# SCH.net
KiCad netlist of a schematic drawn in EasyEDA
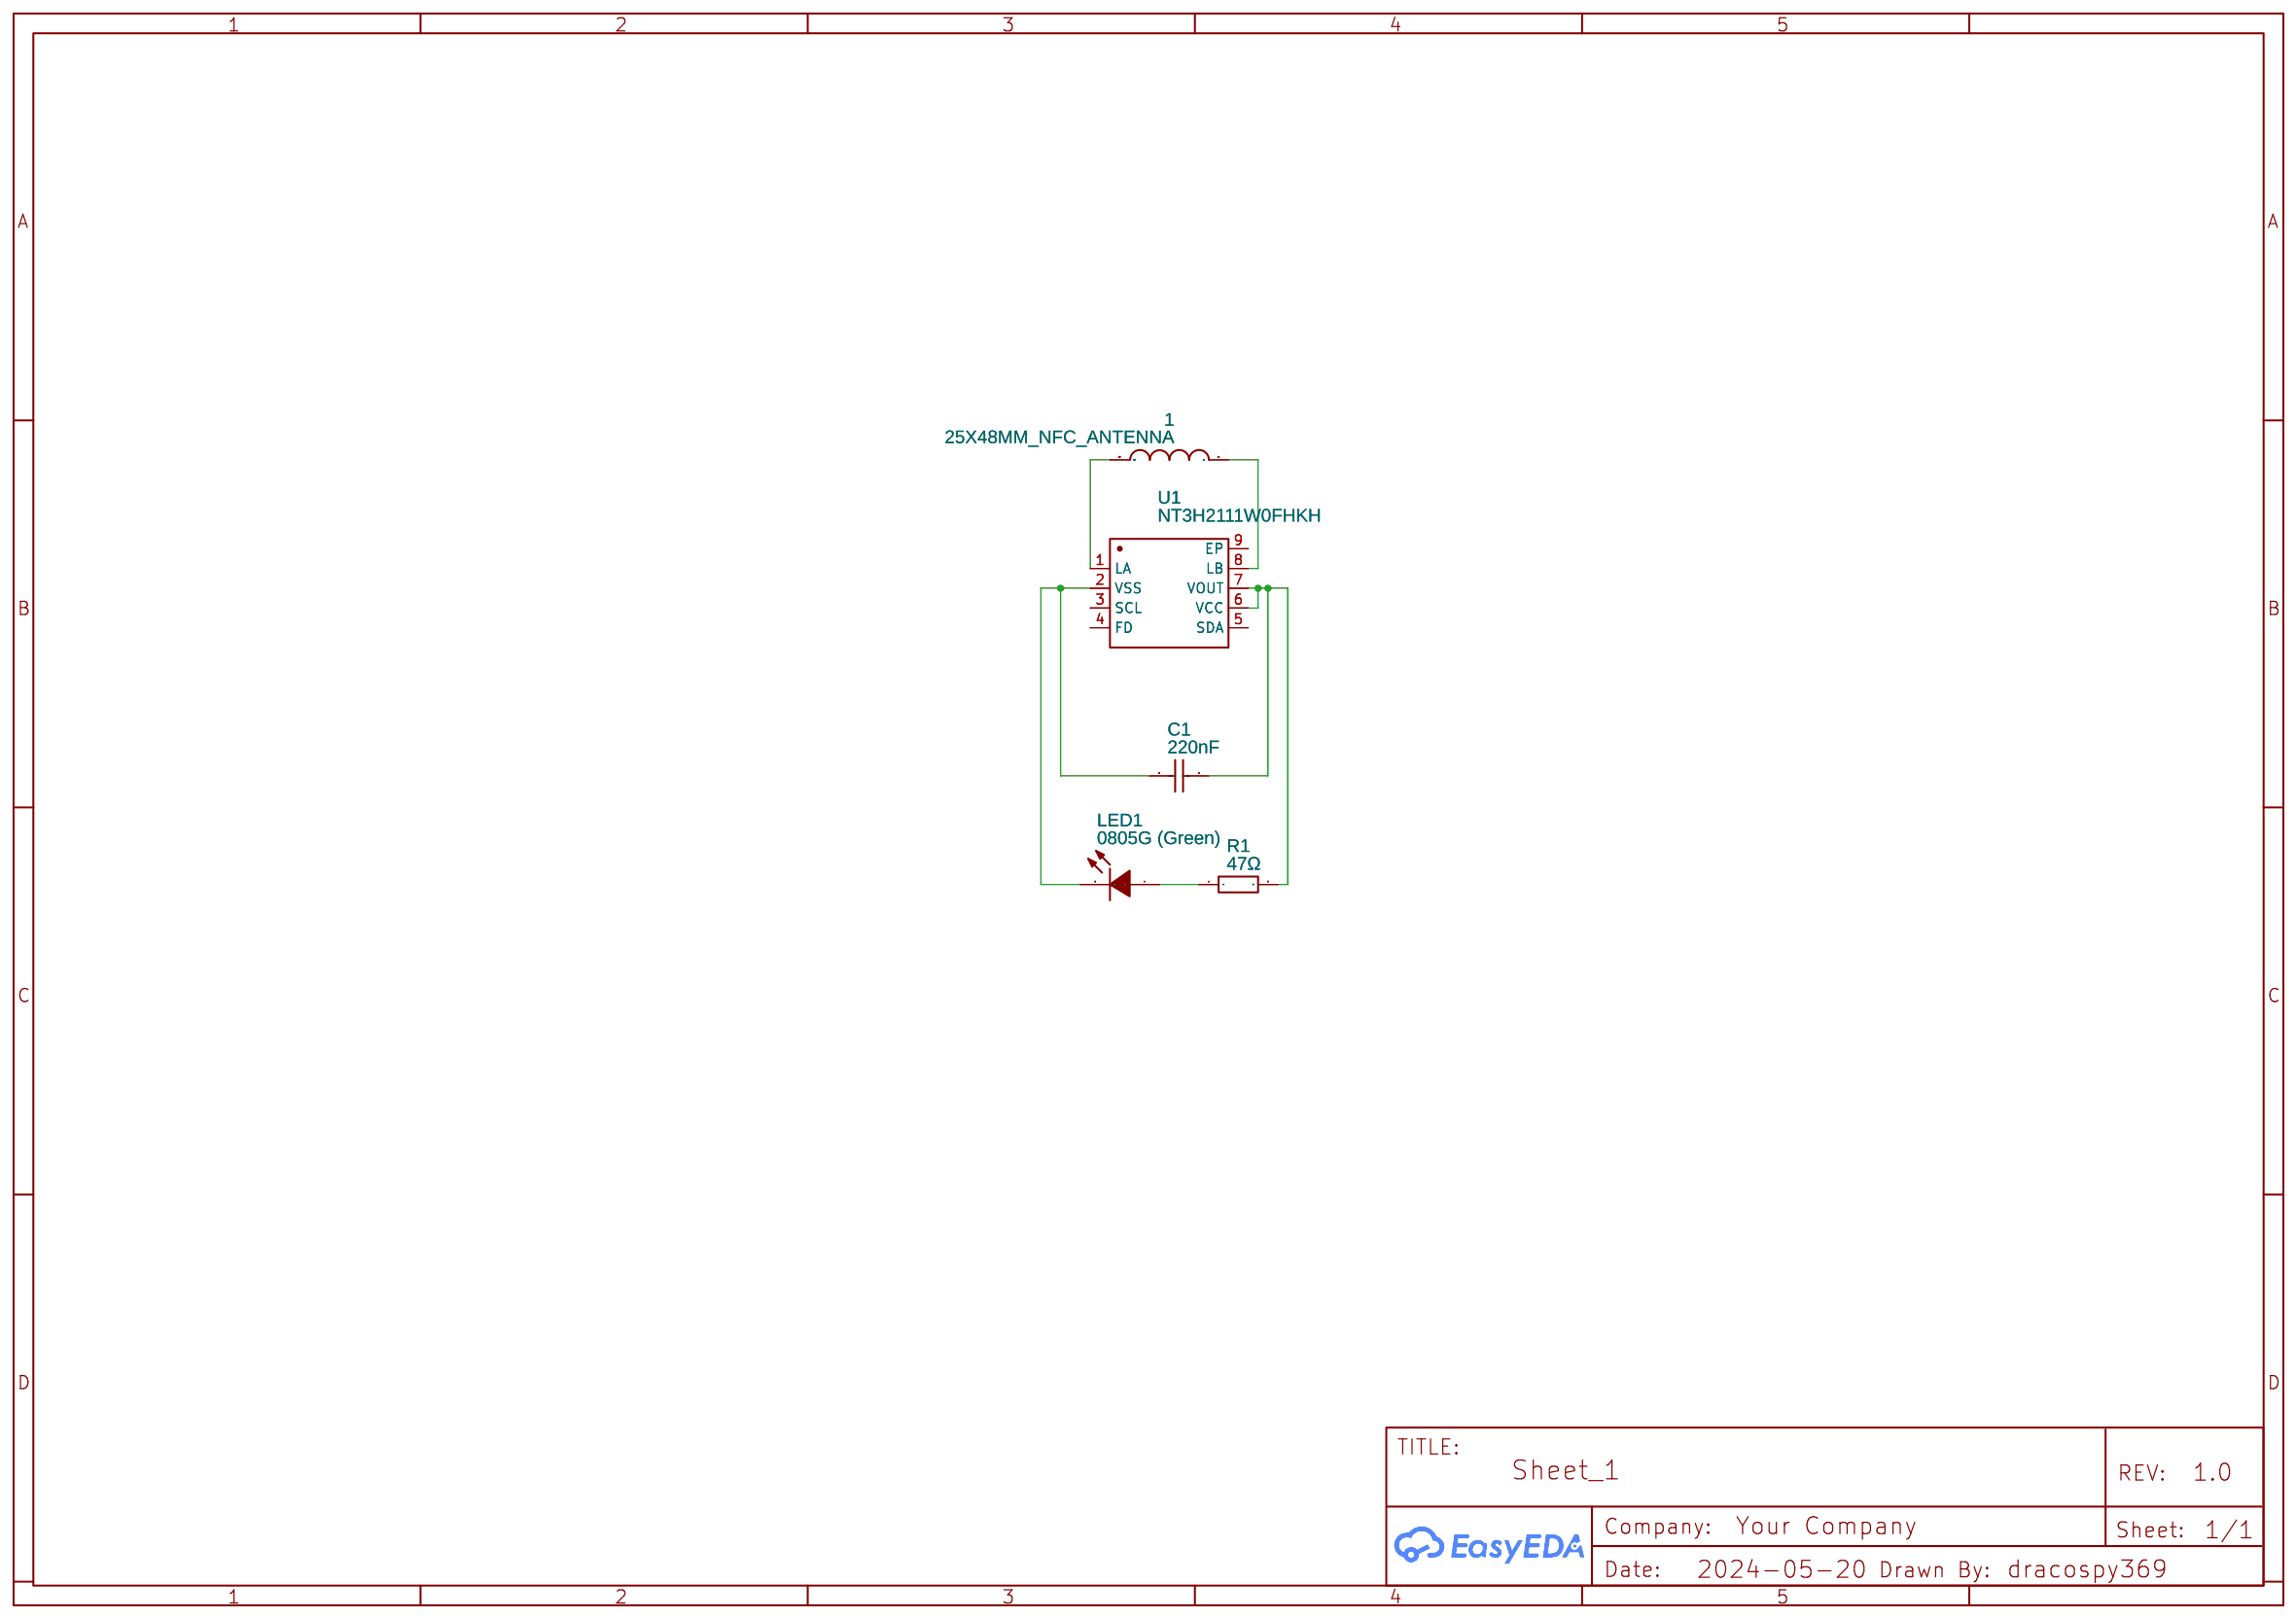
[diagram p0: schematic sheet]

(export (version "E")
  (design (tool "Eeschema 10.0.6"))
  (components
    (comp (ref "1") (value "25X48MM_NFC_ANTENNA") (libsource (lib "") (part "25X48MM_NFC_ANTENNA")))
    (comp (ref "C1")
      (value "220nF")
      (fields
        (field (name "Manufacturer Part") "CL10B224KA8NNNC")
        (field (name "Manufacturer") "SAMSUNG(三星)")
      )
      (libsource (lib "") (part "CL10B224KA8NNNC"))
    )
    (comp (ref "LED1")
      (value "0805G (Green)")
      (fields (field (name "Manufacturer Part") "KT-0805G") (field (name "Manufacturer") "KENTO"))
      (libsource (lib "") (part "0805G (Green)"))
    )
    (comp (ref "R1")
      (value "47Ω")
      (fields
        (field (name "Manufacturer Part") "0603WAF470JT5E")
        (field (name "Manufacturer") "UNI-ROYAL(厚声)")
      )
      (libsource (lib "") (part "0603WAF470JT5E"))
    )
    (comp (ref "U1")
      (value "NT3H2111W0FHKH")
      (fields (field (name "Manufacturer") "NXP(恩智浦)"))
      (libsource (lib "") (part "NT3H2111W0FHKH"))
    )
  )
  (nets
    (net (code "1") (name "Net-(LED1-A)") (class "Default")
      (node (ref "LED1") (pin "1") (pinfunction "A_1") (pintype "unspecified"))
      (node (ref "R1") (pin "1") (pinfunction "1_1") (pintype "input"))
    )
    (net (code "2") (name "Net-(LED1-K)") (class "Default")
      (node (ref "C1") (pin "1") (pinfunction "1_1") (pintype "input"))
      (node (ref "LED1") (pin "2") (pinfunction "K_2") (pintype "unspecified"))
      (node (ref "U1") (pin "2") (pinfunction "VSS_2") (pintype "unspecified"))
    )
    (net (code "3") (name "Net-(U1-LA)") (class "Default")
      (node (ref "1") (pin "P$2") (pinfunction "P$2_P$2") (pintype "bidirectional"))
      (node (ref "U1") (pin "1") (pinfunction "LA_1") (pintype "unspecified"))
    )
    (net (code "4") (name "Net-(U1-LB)") (class "Default")
      (node (ref "1") (pin "P$1") (pinfunction "P$1_P$1") (pintype "bidirectional"))
      (node (ref "U1") (pin "8") (pinfunction "LB_8") (pintype "unspecified"))
    )
    (net (code "5") (name "Net-(U1-VCC)") (class "Default")
      (node (ref "C1") (pin "2") (pinfunction "2_2") (pintype "input"))
      (node (ref "R1") (pin "2") (pinfunction "2_2") (pintype "input"))
      (node (ref "U1") (pin "6") (pinfunction "VCC_6") (pintype "unspecified"))
      (node (ref "U1") (pin "7") (pinfunction "VOUT_7") (pintype "unspecified"))
    )
    (net (code "6") (name "unconnected-(U1-EP-Pad9)") (class "Default")
      (node (ref "U1") (pin "9") (pinfunction "EP_9") (pintype "unspecified"))
    )
    (net (code "7") (name "unconnected-(U1-FD-Pad4)") (class "Default")
      (node (ref "U1") (pin "4") (pinfunction "FD_4") (pintype "unspecified"))
    )
    (net (code "8") (name "unconnected-(U1-SCL-Pad3)") (class "Default")
      (node (ref "U1") (pin "3") (pinfunction "SCL_3") (pintype "unspecified"))
    )
    (net (code "9") (name "unconnected-(U1-SDA-Pad5)") (class "Default")
      (node (ref "U1") (pin "5") (pinfunction "SDA_5") (pintype "unspecified"))
    )
  )
)
